# overdischarge_protection.net
KiCad netlist of a schematic drawn in Altium Designer
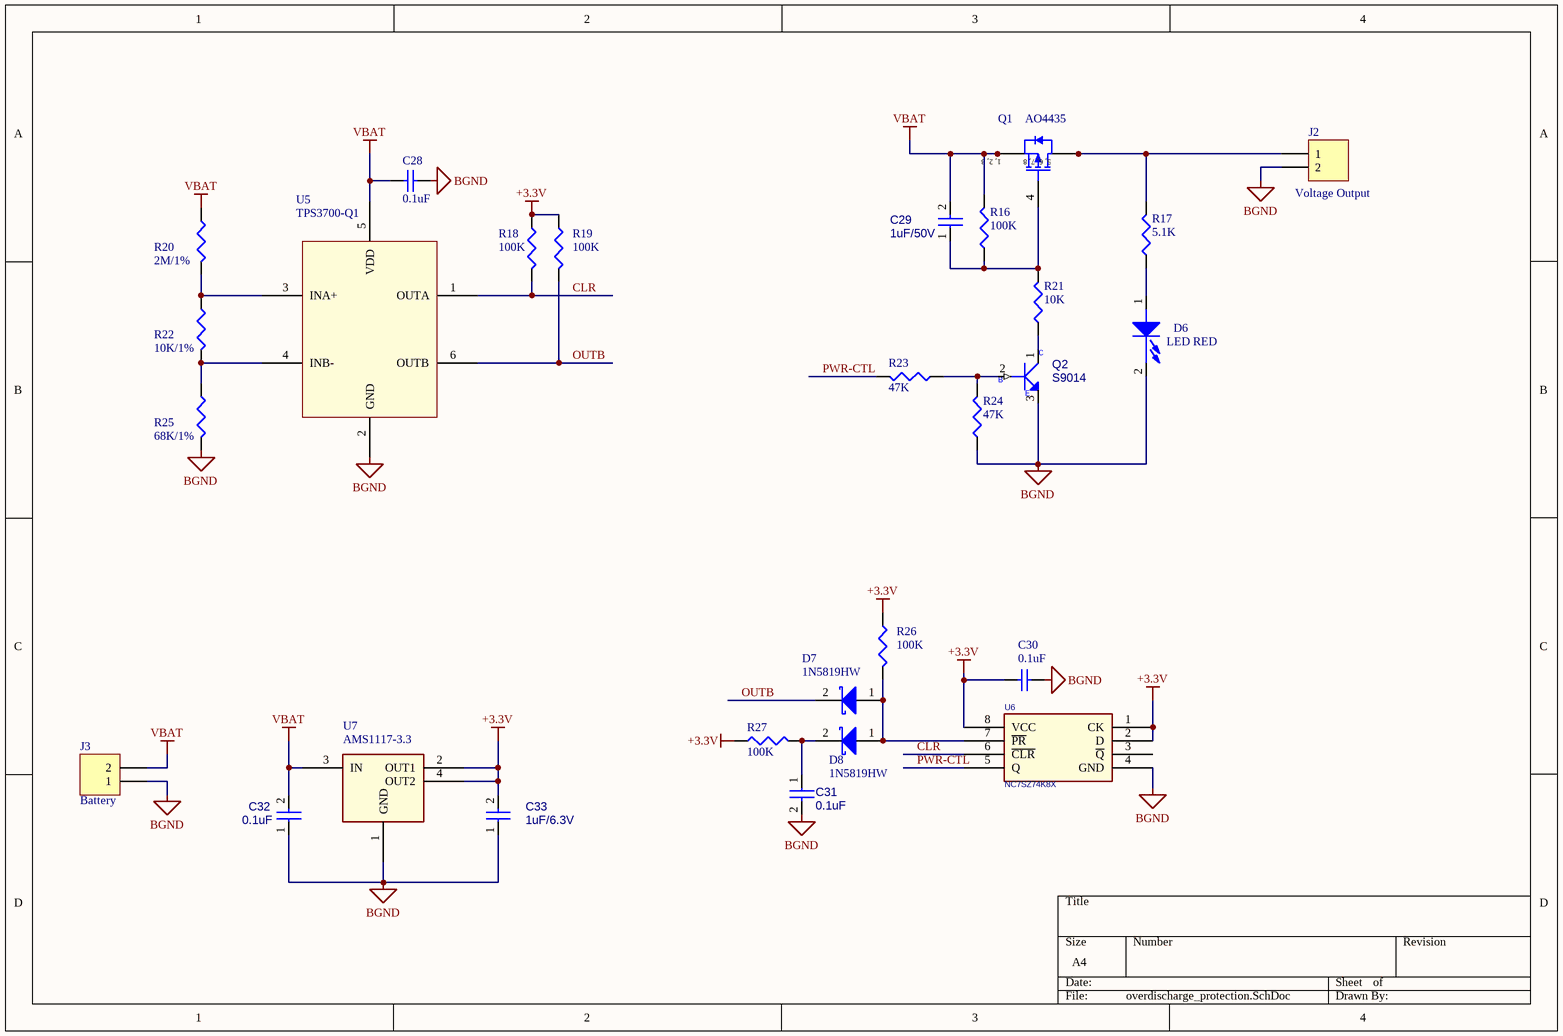
[diagram p0: overdischarge_protection.SchDoc]

(export (version "E")
  (design (tool "Eeschema 10.0.6"))
  (components
    (comp (ref "C28")
      (value "0.1uF")
      (footprint "0603")
      (description "Capacitor")
      (fields (field (name "PUBLISHER") "Altium Limited"))
      (libsource (lib "Miscellaneous Devices") (part "Cap"))
    )
    (comp (ref "C29") (value "1uF/50V") (footprint "1210") (libsource (lib "*") (part "CAP NP_Dup2")))
    (comp (ref "C30")
      (value "0.1uF")
      (footprint "0603")
      (description "Capacitor")
      (fields (field (name "PUBLISHER") "Altium Limited"))
      (libsource (lib "Miscellaneous Devices") (part "Cap"))
    )
    (comp (ref "C31") (value "0.1uF") (footprint "0603") (libsource (lib "*") (part "CAP NP_Dup2")))
    (comp (ref "C32") (value "0.1uF") (footprint "0603") (libsource (lib "*") (part "CAP NP_Dup2")))
    (comp (ref "C33") (value "1uF/6.3V") (footprint "0603") (libsource (lib "*") (part "CAP NP_Dup2")))
    (comp (ref "D6") (value "LED RED") (footprint "LED0603") (libsource (lib "*") (part "LN01401_1")))
    (comp (ref "D7")
      (value "1N5819HW")
      (footprint "1N5819")
      (description "Schottky Rectifier")
      (libsource (lib "Miscellaneous Devices") (part "Diode 11DQ03"))
    )
    (comp (ref "D8")
      (value "1N5819HW")
      (footprint "1N5819")
      (description "Schottky Rectifier")
      (libsource (lib "Miscellaneous Devices") (part "Diode 11DQ03"))
    )
    (comp (ref "J2")
      (value "Voltage Output")
      (footprint "T-2PIN")
      (description "Header, 2-Pin")
      (fields (field (name "PUBLISHER") "Altium Limited"))
      (libsource (lib "Miscellaneous Connectors") (part "Header 2"))
    )
    (comp (ref "J3")
      (value "Battery")
      (footprint "T-2PIN")
      (description "Header, 2-Pin")
      (fields (field (name "PUBLISHER") "Altium Limited"))
      (libsource (lib "") (part "Header 2_1"))
    )
    (comp (ref "Q1")
      (value "AO4435")
      (footprint "SO8")
      (description "P-Channel 30V (D-S)  MOSFET")
      (fields (field (name "PUBLISHER") "Altium Limited"))
      (libsource (lib "Vishay Siliconix Discrete MOSFET") (part "SI4431DY"))
    )
    (comp (ref "Q2")
      (value "S9014")
      (footprint "NPN")
      (fields (field (name "PART NUMBER") "SB039040000"))
      (libsource (lib "*") (part "MMBT3904_NL_SOT23-3"))
    )
    (comp (ref "R16") (value "100K") (footprint "0603") (libsource (lib "*") (part "CR16-1003FM")))
    (comp (ref "R17") (value "5.1K") (footprint "0603") (libsource (lib "*") (part "CR16-1003FM")))
    (comp (ref "R18")
      (value "100K")
      (footprint "0603")
      (description "Resistor")
      (fields (field (name "PUBLISHER") "Altium Limited"))
      (libsource (lib "Miscellaneous Devices") (part "Res3"))
    )
    (comp (ref "R19")
      (value "100K")
      (footprint "0603")
      (description "Resistor")
      (fields (field (name "PUBLISHER") "Altium Limited"))
      (libsource (lib "Miscellaneous Devices") (part "Res3"))
    )
    (comp (ref "R20")
      (value "2M/1%")
      (footprint "0603")
      (description "Resistor")
      (fields (field (name "PUBLISHER") "Altium Limited"))
      (libsource (lib "Miscellaneous Devices") (part "Res3"))
    )
    (comp (ref "R21") (value "10K") (footprint "0603") (libsource (lib "*") (part "CR16-1003FM")))
    (comp (ref "R22")
      (value "10K/1%")
      (footprint "0603")
      (description "Resistor")
      (fields (field (name "PUBLISHER") "Altium Limited"))
      (libsource (lib "Miscellaneous Devices") (part "Res3"))
    )
    (comp (ref "R23") (value "47K") (footprint "0603") (libsource (lib "*") (part "CR16-1003FM")))
    (comp (ref "R24") (value "47K") (footprint "0603") (libsource (lib "*") (part "CR16-1003FM")))
    (comp (ref "R25")
      (value "68K/1%")
      (footprint "0603")
      (description "Resistor")
      (fields (field (name "PUBLISHER") "Altium Limited"))
      (libsource (lib "Miscellaneous Devices") (part "Res3"))
    )
    (comp (ref "R26")
      (value "100K")
      (footprint "0603")
      (description "Resistor")
      (fields (field (name "PUBLISHER") "Altium Limited"))
      (libsource (lib "Miscellaneous Devices") (part "Res3"))
    )
    (comp (ref "R27")
      (value "100K")
      (footprint "0603")
      (description "Resistor")
      (fields (field (name "PUBLISHER") "Altium Limited"))
      (libsource (lib "Miscellaneous Devices") (part "Res3"))
    )
    (comp (ref "U5")
      (value "TPS3700-Q1")
      (footprint "SOT23-6")
      (libsource (lib "Schlib") (part "TPS3700-Q1"))
    )
    (comp (ref "U6")
      (value "NC7SZ74K8X")
      (footprint "US8")
      (description "IC;NC7SZ74,D-TYPE FLIP-FLOP,US8")
      (libsource (lib "*") (part "NC7SZ74-US8_0"))
    )
    (comp (ref "U7")
      (value "AMS1117-3.3")
      (footprint "AMS1117")
      (libsource (lib "*") (part "LT1963EST-1_4.8"))
    )
  )
  (nets
    (net (code "1") (name "+3.3V") (class "Default")
      (node (ref "C30") (pin "2") (pinfunction "2_2") (pintype "passive"))
      (node (ref "C33") (pin "2") (pinfunction "2_2") (pintype "passive"))
      (node (ref "R18") (pin "1") (pinfunction "1_1") (pintype "passive"))
      (node (ref "R19") (pin "1") (pinfunction "1_1") (pintype "passive"))
      (node (ref "R26") (pin "1") (pinfunction "1_1") (pintype "passive"))
      (node (ref "R27") (pin "1") (pinfunction "1_1") (pintype "passive"))
      (node (ref "U6") (pin "1") (pinfunction "CK_1") (pintype "passive"))
      (node (ref "U6") (pin "2") (pinfunction "D_2") (pintype "passive"))
      (node (ref "U6") (pin "8") (pinfunction "VCC_8") (pintype "passive"))
      (node (ref "U7") (pin "2") (pinfunction "OUT1_2") (pintype "passive"))
      (node (ref "U7") (pin "4") (pinfunction "OUT2_4") (pintype "passive"))
    )
    (net (code "2") (name "/CLR") (class "Default")
      (node (ref "R18") (pin "2") (pinfunction "2_2") (pintype "passive"))
      (node (ref "U5") (pin "1") (pinfunction "OUTA_1") (pintype "passive"))
      (node (ref "U6") (pin "6") (pinfunction "~{CLR}_6") (pintype "passive"))
    )
    (net (code "3") (name "/OUTB") (class "Default")
      (node (ref "D7") (pin "2") (pinfunction "K_2") (pintype "passive"))
      (node (ref "R19") (pin "2") (pinfunction "2_2") (pintype "passive"))
      (node (ref "U5") (pin "6") (pinfunction "OUTB_6") (pintype "passive"))
    )
    (net (code "4") (name "/PWR-CTL") (class "Default")
      (node (ref "R23") (pin "2") (pinfunction "2_2") (pintype "passive"))
      (node (ref "U6") (pin "5") (pinfunction "Q_5") (pintype "passive"))
    )
    (net (code "5") (name "BGND") (class "Default")
      (node (ref "C28") (pin "1") (pinfunction "1_1") (pintype "passive"))
      (node (ref "C30") (pin "1") (pinfunction "1_1") (pintype "passive"))
      (node (ref "C31") (pin "2") (pinfunction "2_2") (pintype "passive"))
      (node (ref "C32") (pin "1") (pinfunction "1_1") (pintype "passive"))
      (node (ref "C33") (pin "1") (pinfunction "1_1") (pintype "passive"))
      (node (ref "D6") (pin "2") (pinfunction "CATHODE_2") (pintype "passive"))
      (node (ref "J2") (pin "2") (pinfunction "2_2") (pintype "passive"))
      (node (ref "J3") (pin "1") (pinfunction "1_1") (pintype "passive"))
      (node (ref "Q2") (pin "3") (pinfunction "EMITTER_3") (pintype "passive"))
      (node (ref "R24") (pin "1") (pinfunction "1_1") (pintype "passive"))
      (node (ref "R25") (pin "2") (pinfunction "2_2") (pintype "passive"))
      (node (ref "U5") (pin "2") (pinfunction "GND_2") (pintype "passive"))
      (node (ref "U6") (pin "4") (pinfunction "GND_4") (pintype "passive"))
      (node (ref "U7") (pin "1") (pinfunction "GND_1") (pintype "passive"))
    )
    (net (code "6") (name "Net-(D6-ANODE)") (class "Default")
      (node (ref "D6") (pin "1") (pinfunction "ANODE_1") (pintype "passive"))
      (node (ref "R17") (pin "1") (pinfunction "1_1") (pintype "passive"))
    )
    (net (code "7") (name "Net-(D7-A)") (class "Default")
      (node (ref "D7") (pin "1") (pinfunction "A_1") (pintype "passive"))
      (node (ref "D8") (pin "1") (pinfunction "A_1") (pintype "passive"))
      (node (ref "R26") (pin "2") (pinfunction "2_2") (pintype "passive"))
      (node (ref "U6") (pin "7") (pinfunction "~{PR}_7") (pintype "passive"))
    )
    (net (code "8") (name "Net-(D8-K)") (class "Default")
      (node (ref "C31") (pin "1") (pinfunction "1_1") (pintype "passive"))
      (node (ref "D8") (pin "2") (pinfunction "K_2") (pintype "passive"))
      (node (ref "R27") (pin "2") (pinfunction "2_2") (pintype "passive"))
    )
    (net (code "9") (name "Net-(J2-Pad1)") (class "Default")
      (node (ref "J2") (pin "1") (pinfunction "1_1") (pintype "passive"))
      (node (ref "Q1") (pin "5") (pinfunction "D_5") (pintype "passive"))
      (node (ref "Q1") (pin "6") (pinfunction "D_6") (pintype "passive"))
      (node (ref "Q1") (pin "7") (pinfunction "D_7") (pintype "passive"))
      (node (ref "Q1") (pin "8") (pinfunction "D_8") (pintype "passive"))
      (node (ref "R17") (pin "2") (pinfunction "2_2") (pintype "passive"))
    )
    (net (code "10") (name "Net-(Q1-G)") (class "Default")
      (node (ref "C29") (pin "1") (pinfunction "1_1") (pintype "passive"))
      (node (ref "Q1") (pin "4") (pinfunction "G_4") (pintype "passive"))
      (node (ref "R16") (pin "1") (pinfunction "1_1") (pintype "passive"))
      (node (ref "R21") (pin "2") (pinfunction "2_2") (pintype "passive"))
    )
    (net (code "11") (name "Net-(Q2-BASE)") (class "Default")
      (node (ref "Q2") (pin "2") (pinfunction "BASE_2") (pintype "input"))
      (node (ref "R23") (pin "1") (pinfunction "1_1") (pintype "passive"))
      (node (ref "R24") (pin "2") (pinfunction "2_2") (pintype "passive"))
    )
    (net (code "12") (name "Net-(Q2-COLLECTOR)") (class "Default")
      (node (ref "Q2") (pin "1") (pinfunction "COLLECTOR_1") (pintype "passive"))
      (node (ref "R21") (pin "1") (pinfunction "1_1") (pintype "passive"))
    )
    (net (code "13") (name "Net-(U5-INA+)") (class "Default")
      (node (ref "R20") (pin "2") (pinfunction "2_2") (pintype "passive"))
      (node (ref "R22") (pin "1") (pinfunction "1_1") (pintype "passive"))
      (node (ref "U5") (pin "3") (pinfunction "INA+_3") (pintype "passive"))
    )
    (net (code "14") (name "Net-(U5-INB-)") (class "Default")
      (node (ref "R22") (pin "2") (pinfunction "2_2") (pintype "passive"))
      (node (ref "R25") (pin "1") (pinfunction "1_1") (pintype "passive"))
      (node (ref "U5") (pin "4") (pinfunction "INB-_4") (pintype "passive"))
    )
    (net (code "15") (name "VBAT") (class "Default")
      (node (ref "C28") (pin "2") (pinfunction "2_2") (pintype "passive"))
      (node (ref "C29") (pin "2") (pinfunction "2_2") (pintype "passive"))
      (node (ref "C32") (pin "2") (pinfunction "2_2") (pintype "passive"))
      (node (ref "J3") (pin "2") (pinfunction "2_2") (pintype "passive"))
      (node (ref "Q1") (pin "1") (pinfunction "S_1") (pintype "passive"))
      (node (ref "Q1") (pin "2") (pinfunction "S_2") (pintype "passive"))
      (node (ref "Q1") (pin "3") (pinfunction "S_3") (pintype "passive"))
      (node (ref "R16") (pin "2") (pinfunction "2_2") (pintype "passive"))
      (node (ref "R20") (pin "1") (pinfunction "1_1") (pintype "passive"))
      (node (ref "U5") (pin "5") (pinfunction "VDD_5") (pintype "passive"))
      (node (ref "U7") (pin "3") (pinfunction "IN_3") (pintype "passive"))
    )
    (net (code "16") (name "unconnected-(U6-~{Q}-Pad3)") (class "Default")
      (node (ref "U6") (pin "3") (pinfunction "~{Q}_3") (pintype "passive"))
    )
  )
)
